# hib_main_7.net
KiCad netlist of a schematic drawn in EAGLE
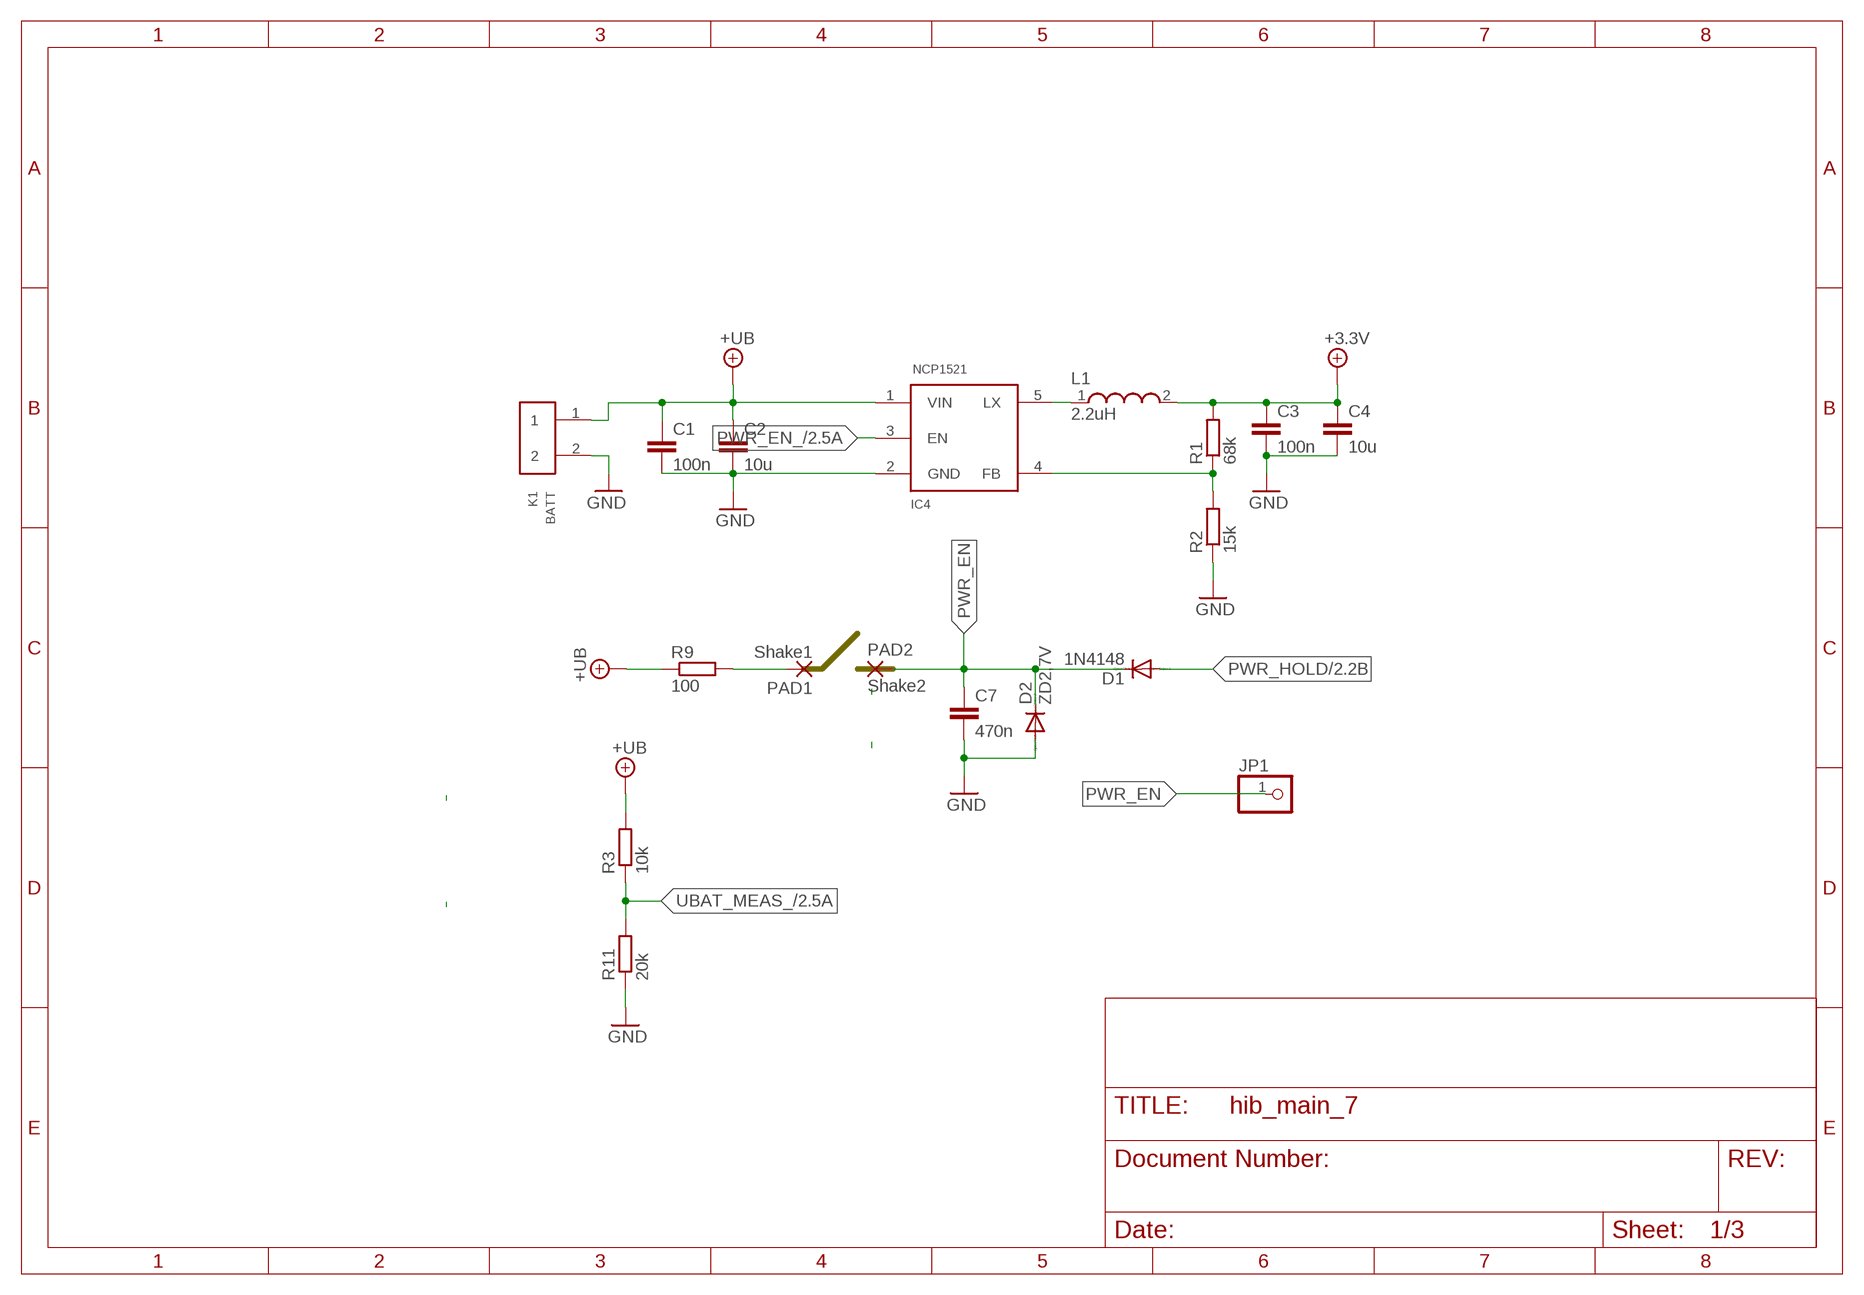
[diagram p0: schematic, sheet 1]
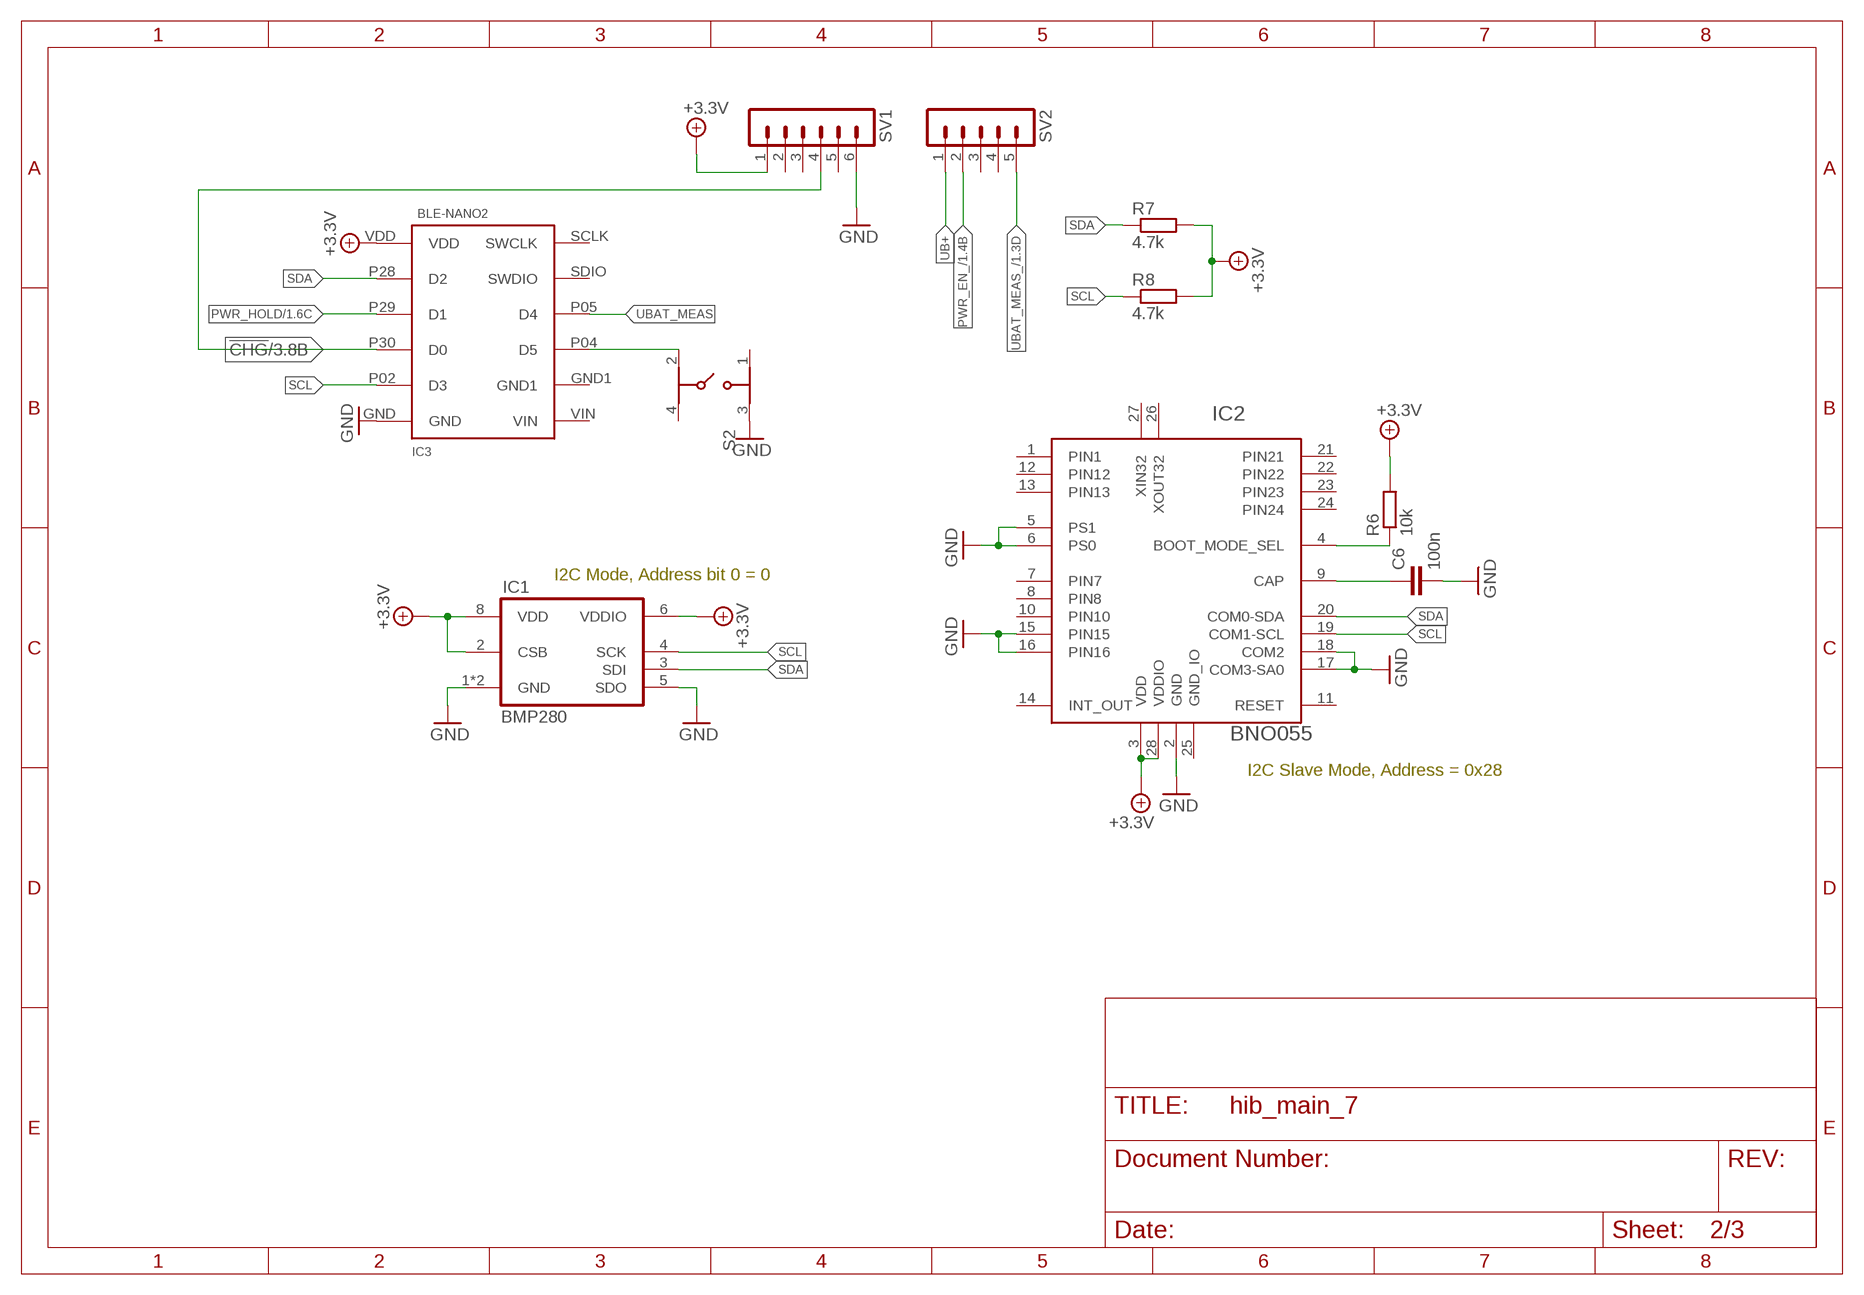
[diagram p1: schematic, sheet 2]
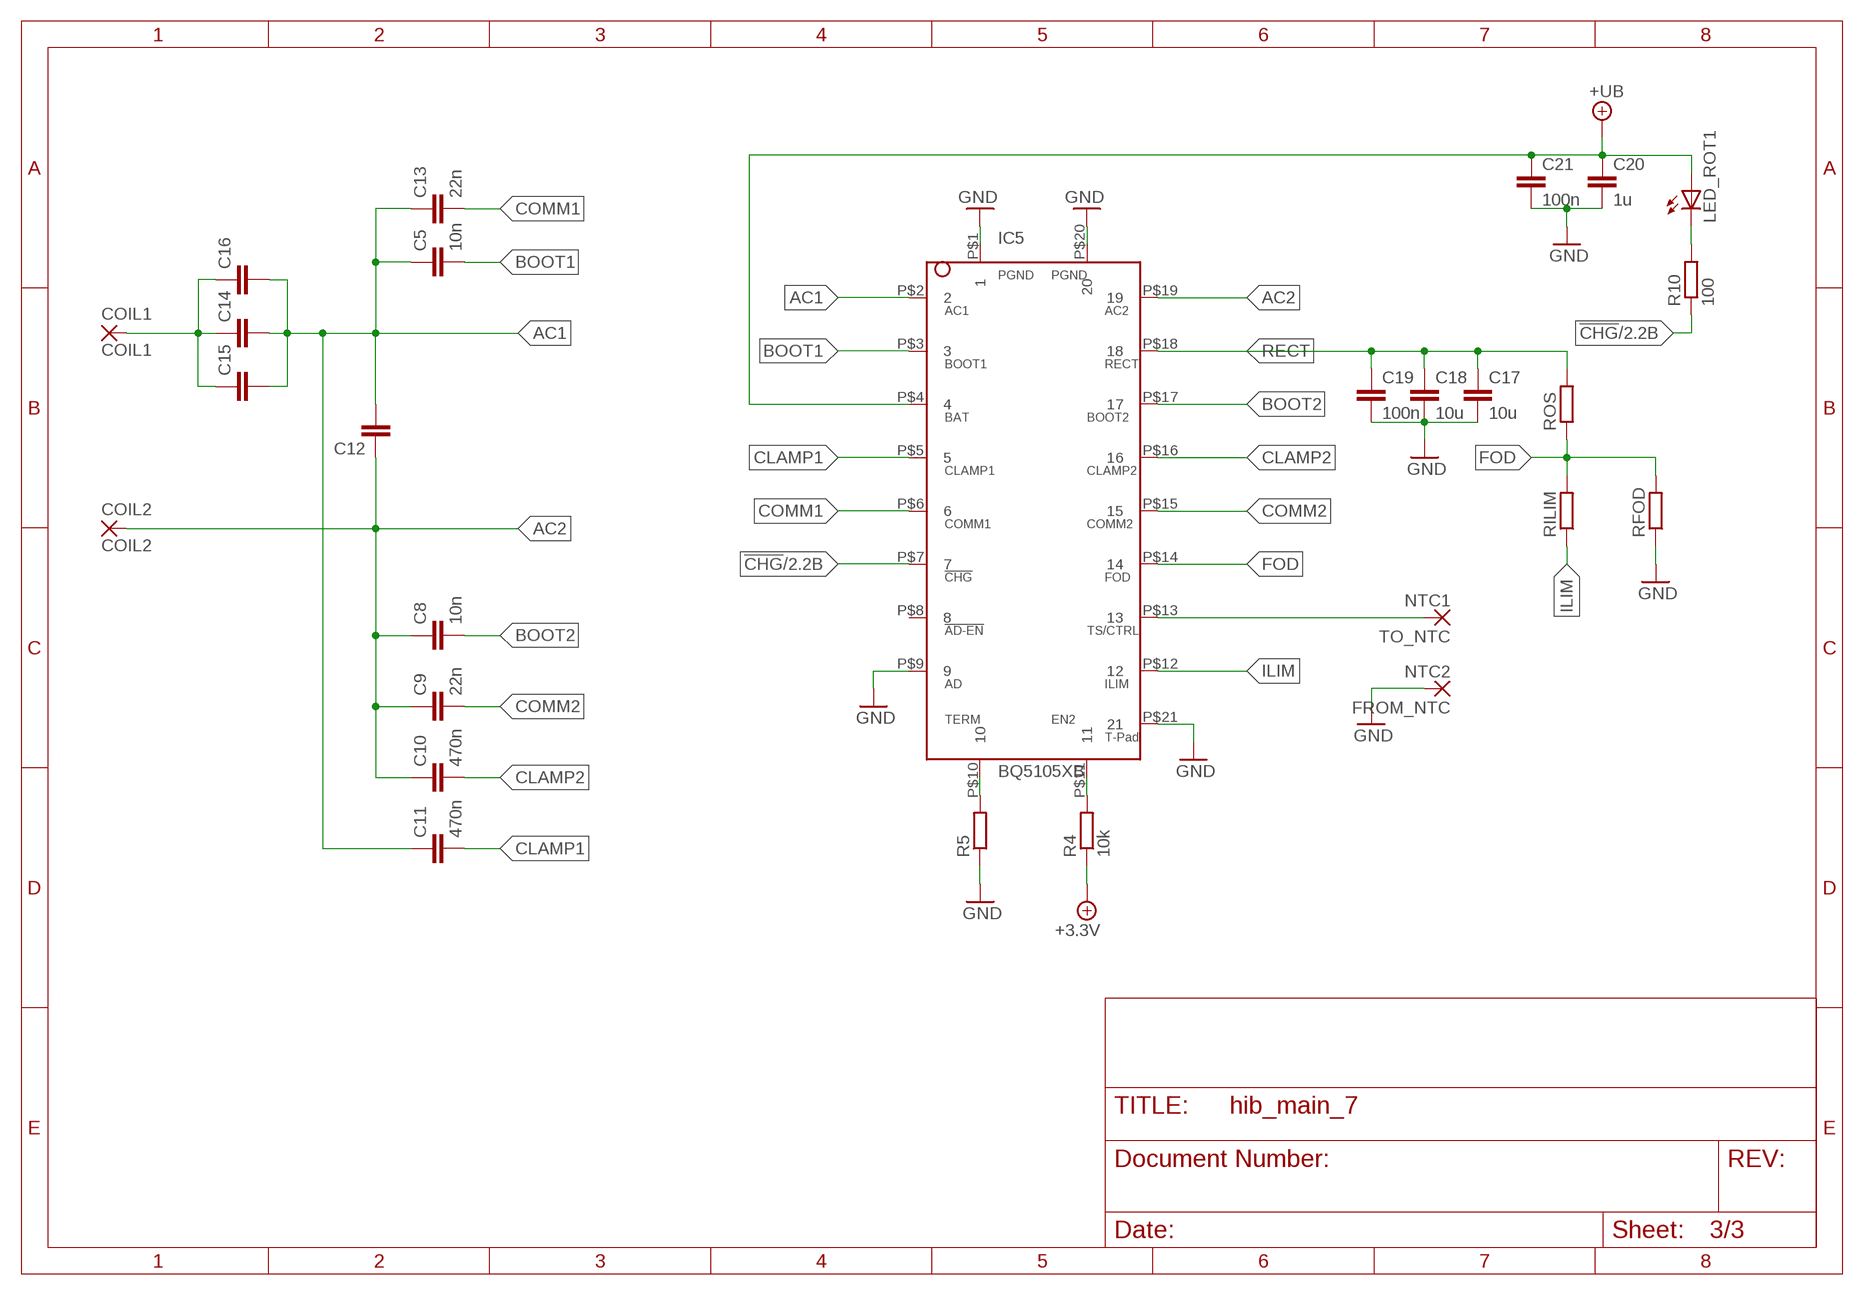
[diagram p2: schematic, sheet 3]

(export (version "E")
  (design (tool "Eeschema 10.0.6"))
  (components
    (comp (ref "C5")
      (value "10n")
      (footprint "eagle-import:C0603K")
      (libsource (lib "eagle-import") (part "rcl@1_C-EUC0603K"))
    )
    (comp (ref "C8")
      (value "10n")
      (footprint "eagle-import:C0603K")
      (libsource (lib "eagle-import") (part "rcl@1_C-EUC0603K"))
    )
    (comp (ref "C9")
      (value "22n")
      (footprint "eagle-import:C0603K")
      (libsource (lib "eagle-import") (part "rcl@1_C-EUC0603K"))
    )
    (comp (ref "C10")
      (value "470n")
      (footprint "eagle-import:C0603K")
      (libsource (lib "eagle-import") (part "rcl@1_C-EUC0603K"))
    )
    (comp (ref "C11")
      (value "470n")
      (footprint "eagle-import:C0603K")
      (libsource (lib "eagle-import") (part "rcl@1_C-EUC0603K"))
    )
    (comp (ref "C12")
      (value "C-EUC0603K")
      (footprint "eagle-import:C0603K")
      (libsource (lib "eagle-import") (part "rcl@1_C-EUC0603K"))
    )
    (comp (ref "C13")
      (value "22n")
      (footprint "eagle-import:C0603K")
      (libsource (lib "eagle-import") (part "rcl@1_C-EUC0603K"))
    )
    (comp (ref "C14")
      (value "C-EUC0603K")
      (footprint "eagle-import:C0603K")
      (libsource (lib "eagle-import") (part "rcl@1_C-EUC0603K"))
    )
    (comp (ref "C15")
      (value "C-EUC0603K")
      (footprint "eagle-import:C0603K")
      (libsource (lib "eagle-import") (part "rcl@1_C-EUC0603K"))
    )
    (comp (ref "C16")
      (value "C-EUC0603K")
      (footprint "eagle-import:C0603K")
      (libsource (lib "eagle-import") (part "rcl@1_C-EUC0603K"))
    )
    (comp (ref "C17")
      (value "10u")
      (footprint "eagle-import:C0603K")
      (libsource (lib "eagle-import") (part "rcl@1_C-EUC0603K"))
    )
    (comp (ref "C18")
      (value "10u")
      (footprint "eagle-import:C0603K")
      (libsource (lib "eagle-import") (part "rcl@1_C-EUC0603K"))
    )
    (comp (ref "C19")
      (value "100n")
      (footprint "eagle-import:C0603K")
      (libsource (lib "eagle-import") (part "rcl@1_C-EUC0603K"))
    )
    (comp (ref "C20")
      (value "1u")
      (footprint "eagle-import:C0603K")
      (libsource (lib "eagle-import") (part "rcl@1_C-EUC0603K"))
    )
    (comp (ref "C21")
      (value "100n")
      (footprint "eagle-import:C0603K")
      (libsource (lib "eagle-import") (part "rcl@1_C-EUC0603K"))
    )
    (comp (ref "COIL1")
      (value "COIL1")
      (footprint "eagle-import:SMD1,27-2,54")
      (libsource (lib "eagle-import") (part "wirepad@1_WIREPADSMD1,27-254"))
    )
    (comp (ref "COIL2")
      (value "COIL2")
      (footprint "eagle-import:SMD1,27-2,54")
      (libsource (lib "eagle-import") (part "wirepad@1_WIREPADSMD1,27-254"))
    )
    (comp (ref "FROM_NTC")
      (value "NTC2")
      (footprint "eagle-import:SMD1,27-2,54")
      (libsource (lib "eagle-import") (part "wirepad@1_WIREPADSMD1,27-254"))
    )
    (comp (ref "IC5")
      (value "BQ5105XB")
      (footprint "eagle-import:VQFN_BQ5105B")
      (libsource (lib "eagle-import") (part "BQ5105XB"))
    )
    (comp (ref "LED_ROT1")
      (value "LEDCHIP-LED0603")
      (footprint "eagle-import:CHIP-LED0603")
      (libsource (lib "eagle-import") (part "LEDCHIP-LED0603"))
    )
    (comp (ref "R4")
      (value "10k")
      (footprint "eagle-import:R0805")
      (libsource (lib "eagle-import") (part "rcl@1_R-EU_R0805"))
    )
    (comp (ref "R5")
      (value "R-EU_R0603")
      (footprint "eagle-import:R0603")
      (libsource (lib "eagle-import") (part "rcl@1_R-EU_R0603"))
    )
    (comp (ref "R10")
      (value "100")
      (footprint "eagle-import:R0603")
      (libsource (lib "eagle-import") (part "rcl@1_R-EU_R0603"))
    )
    (comp (ref "RFOD")
      (value "R-EU_R0805")
      (footprint "eagle-import:R0805")
      (libsource (lib "eagle-import") (part "rcl@1_R-EU_R0805"))
    )
    (comp (ref "RILIM")
      (value "R-EU_R0805")
      (footprint "eagle-import:R0805")
      (libsource (lib "eagle-import") (part "rcl@1_R-EU_R0805"))
    )
    (comp (ref "ROS")
      (value "R-EU_R0805")
      (footprint "eagle-import:R0805")
      (libsource (lib "eagle-import") (part "rcl@1_R-EU_R0805"))
    )
    (comp (ref "TO_NTC")
      (value "NTC1")
      (footprint "eagle-import:SMD1,27-2,54")
      (libsource (lib "eagle-import") (part "wirepad@1_WIREPADSMD1,27-254"))
    )
    (comp (ref "C1")
      (value "100n")
      (footprint "eagle-import:C0805K")
      (libsource (lib "eagle-import") (part "rcl@1_C-EUC0805K"))
    )
    (comp (ref "C2")
      (value "10u")
      (footprint "eagle-import:C0805K")
      (libsource (lib "eagle-import") (part "rcl@1_C-EUC0805K"))
    )
    (comp (ref "C3")
      (value "100n")
      (footprint "eagle-import:C0805M")
      (libsource (lib "eagle-import") (part "C-EUC0805M"))
    )
    (comp (ref "C4")
      (value "10u")
      (footprint "eagle-import:C0805M")
      (libsource (lib "eagle-import") (part "C-EUC0805M"))
    )
    (comp (ref "C7")
      (value "470n")
      (footprint "eagle-import:C0805M")
      (libsource (lib "eagle-import") (part "C-EUC0805M"))
    )
    (comp (ref "D1")
      (value "1N4148")
      (footprint "eagle-import:MINIMELF")
      (libsource (lib "eagle-import") (part "DIODE-MINIMELF"))
    )
    (comp (ref "D2")
      (value "ZD2,7V")
      (footprint "eagle-import:MINIMELF")
      (libsource (lib "eagle-import") (part "DIODE-MINIMELF"))
    )
    (comp (ref "IC4")
      (value "NCP1521")
      (footprint "eagle-import:SOT23-5L")
      (libsource (lib "eagle-import") (part "NCP1521"))
    )
    (comp (ref "JP1")
      (value "PINHD-1X1")
      (footprint "eagle-import:1X01")
      (libsource (lib "eagle-import") (part "PINHD-1X1"))
    )
    (comp (ref "K1")
      (value "BATT")
      (footprint "eagle-import:620102131822")
      (libsource (lib "eagle-import") (part "620102131822"))
    )
    (comp (ref "L1")
      (value "2.2uH")
      (footprint "eagle-import:WE-MPSB_0805(W=4.0)")
      (libsource (lib "eagle-import") (part "WE-MPSB_0805(HC)"))
    )
    (comp (ref "PAD1")
      (value "Shake1")
      (footprint "eagle-import:SMD1,27-2,54")
      (libsource (lib "eagle-import") (part "WIREPADSMD1,27-254"))
    )
    (comp (ref "PAD2")
      (value "Shake2")
      (footprint "eagle-import:SMD1,27-2,54")
      (libsource (lib "eagle-import") (part "WIREPADSMD1,27-254"))
    )
    (comp (ref "R1")
      (value "68k")
      (footprint "eagle-import:R0603")
      (libsource (lib "eagle-import") (part "R-EU_R0603"))
    )
    (comp (ref "R2")
      (value "15k")
      (footprint "eagle-import:R0603")
      (libsource (lib "eagle-import") (part "R-EU_R0603"))
    )
    (comp (ref "R3")
      (value "10k")
      (footprint "eagle-import:R0603")
      (libsource (lib "eagle-import") (part "R-EU_R0603"))
    )
    (comp (ref "R9")
      (value "100")
      (footprint "eagle-import:R0603")
      (libsource (lib "eagle-import") (part "R-EU_R0603"))
    )
    (comp (ref "R11")
      (value "20k")
      (footprint "eagle-import:R0603")
      (libsource (lib "eagle-import") (part "R-EU_R0603"))
    )
    (comp (ref "C6")
      (value "100n")
      (footprint "eagle-import:C0805M")
      (libsource (lib "eagle-import") (part "C-EUC0805M"))
    )
    (comp (ref "IC1")
      (value "BMP280")
      (footprint "eagle-import:BMP280")
      (libsource (lib "eagle-import") (part "BMP280"))
    )
    (comp (ref "IC2")
      (value "BNO055")
      (footprint "eagle-import:LGA-28_3.80X5.20_0.5")
      (libsource (lib "eagle-import") (part "1658_BNO055"))
    )
    (comp (ref "IC3")
      (value "BLE-NANO2")
      (footprint "eagle-import:BLE-NANO2")
      (libsource (lib "eagle-import") (part "BLE-NANO2"))
    )
    (comp (ref "R6")
      (value "10k")
      (footprint "eagle-import:R0805M")
      (libsource (lib "eagle-import") (part "R-EU_R0805M"))
    )
    (comp (ref "R7")
      (value "4.7k")
      (footprint "eagle-import:R0805M")
      (libsource (lib "eagle-import") (part "R-EU_R0805M"))
    )
    (comp (ref "R8")
      (value "4.7k")
      (footprint "eagle-import:R0805M")
      (libsource (lib "eagle-import") (part "R-EU_R0805M"))
    )
    (comp (ref "S2")
      (value "434153017835")
      (footprint "eagle-import:434153017835")
      (libsource (lib "eagle-import") (part "434153017835"))
    )
    (comp (ref "SV1")
      (value "MA06-1")
      (footprint "eagle-import:MA06-1")
      (libsource (lib "eagle-import") (part "MA06-1"))
    )
    (comp (ref "SV2")
      (value "MA05-1")
      (footprint "eagle-import:MA05-1")
      (libsource (lib "eagle-import") (part "MA05-1"))
    )
  )
  (nets
    (net (code "1") (name "+3,3V") (class "Default")
      (node (ref "C3") (pin "1") (pinfunction "1_1") (pintype "passive"))
      (node (ref "C4") (pin "1") (pinfunction "1_1") (pintype "passive"))
      (node (ref "IC1") (pin "2") (pinfunction "CSB_2") (pintype "input"))
      (node (ref "IC1") (pin "6") (pinfunction "VDDIO_6") (pintype "power_in"))
      (node (ref "IC1") (pin "8") (pinfunction "VDD_8") (pintype "power_in"))
      (node (ref "IC2") (pin "28") (pinfunction "VDDIO_28") (pintype "power_in"))
      (node (ref "IC2") (pin "3") (pinfunction "VDD_3") (pintype "power_in"))
      (node (ref "IC3") (pin "VDD") (pinfunction "VDD_VDD") (pintype "bidirectional"))
      (node (ref "L1") (pin "2") (pinfunction "2_2") (pintype "passive"))
      (node (ref "R1") (pin "2") (pinfunction "2_2") (pintype "passive"))
      (node (ref "R4") (pin "1") (pinfunction "1_1") (pintype "passive"))
      (node (ref "R6") (pin "2") (pinfunction "2_2") (pintype "passive"))
      (node (ref "R7") (pin "2") (pinfunction "2_2") (pintype "passive"))
      (node (ref "R8") (pin "2") (pinfunction "2_2") (pintype "passive"))
      (node (ref "SV1") (pin "1") (pinfunction "1_1") (pintype "passive"))
    )
    (net (code "2") (name "+UB") (class "Default")
      (node (ref "C1") (pin "1") (pinfunction "1_1") (pintype "passive"))
      (node (ref "C2") (pin "1") (pinfunction "1_1") (pintype "passive"))
      (node (ref "C20") (pin "1") (pinfunction "1_1") (pintype "passive"))
      (node (ref "C21") (pin "1") (pinfunction "1_1") (pintype "passive"))
      (node (ref "IC4") (pin "1") (pinfunction "VIN_1") (pintype "bidirectional"))
      (node (ref "IC5") (pin "P$4") (pinfunction "4_P$4") (pintype "bidirectional"))
      (node (ref "K1") (pin "1") (pinfunction "1_1") (pintype "passive"))
      (node (ref "LED_ROT1") (pin "A") (pinfunction "A_A") (pintype "passive"))
      (node (ref "R3") (pin "2") (pinfunction "2_2") (pintype "passive"))
      (node (ref "R9") (pin "1") (pinfunction "1_1") (pintype "passive"))
    )
    (net (code "3") (name "AC1") (class "Default")
      (node (ref "C11") (pin "1") (pinfunction "1_1") (pintype "passive"))
      (node (ref "C12") (pin "2") (pinfunction "2_2") (pintype "passive"))
      (node (ref "C13") (pin "1") (pinfunction "1_1") (pintype "passive"))
      (node (ref "C14") (pin "2") (pinfunction "2_2") (pintype "passive"))
      (node (ref "C15") (pin "2") (pinfunction "2_2") (pintype "passive"))
      (node (ref "C16") (pin "2") (pinfunction "2_2") (pintype "passive"))
      (node (ref "C5") (pin "1") (pinfunction "1_1") (pintype "passive"))
      (node (ref "IC5") (pin "P$2") (pinfunction "2_P$2") (pintype "bidirectional"))
    )
    (net (code "4") (name "AC2") (class "Default")
      (node (ref "C10") (pin "1") (pinfunction "1_1") (pintype "passive"))
      (node (ref "C12") (pin "1") (pinfunction "1_1") (pintype "passive"))
      (node (ref "C8") (pin "1") (pinfunction "1_1") (pintype "passive"))
      (node (ref "C9") (pin "1") (pinfunction "1_1") (pintype "passive"))
      (node (ref "COIL2") (pin "1") (pinfunction "P_1") (pintype "passive"))
      (node (ref "IC5") (pin "P$19") (pinfunction "19_P$19") (pintype "bidirectional"))
    )
    (net (code "5") (name "BOOT1") (class "Default")
      (node (ref "C5") (pin "2") (pinfunction "2_2") (pintype "passive"))
      (node (ref "IC5") (pin "P$3") (pinfunction "3_P$3") (pintype "bidirectional"))
    )
    (net (code "6") (name "BOOT2") (class "Default")
      (node (ref "C8") (pin "2") (pinfunction "2_2") (pintype "passive"))
      (node (ref "IC5") (pin "P$17") (pinfunction "17_P$17") (pintype "bidirectional"))
    )
    (net (code "7") (name "CLAMP1") (class "Default")
      (node (ref "C11") (pin "2") (pinfunction "2_2") (pintype "passive"))
      (node (ref "IC5") (pin "P$5") (pinfunction "5_P$5") (pintype "bidirectional"))
    )
    (net (code "8") (name "CLAMP2") (class "Default")
      (node (ref "C10") (pin "2") (pinfunction "2_2") (pintype "passive"))
      (node (ref "IC5") (pin "P$16") (pinfunction "16_P$16") (pintype "bidirectional"))
    )
    (net (code "9") (name "COMM1") (class "Default")
      (node (ref "C13") (pin "2") (pinfunction "2_2") (pintype "passive"))
      (node (ref "IC5") (pin "P$6") (pinfunction "6_P$6") (pintype "bidirectional"))
    )
    (net (code "10") (name "COMM2") (class "Default")
      (node (ref "C9") (pin "2") (pinfunction "2_2") (pintype "passive"))
      (node (ref "IC5") (pin "P$15") (pinfunction "15_P$15") (pintype "bidirectional"))
    )
    (net (code "11") (name "FOD") (class "Default")
      (node (ref "IC5") (pin "P$14") (pinfunction "14_P$14") (pintype "bidirectional"))
      (node (ref "RFOD") (pin "2") (pinfunction "2_2") (pintype "passive"))
      (node (ref "RILIM") (pin "2") (pinfunction "2_2") (pintype "passive"))
      (node (ref "ROS") (pin "1") (pinfunction "1_1") (pintype "passive"))
    )
    (net (code "12") (name "GND") (class "Default")
      (node (ref "C1") (pin "2") (pinfunction "2_2") (pintype "passive"))
      (node (ref "C17") (pin "2") (pinfunction "2_2") (pintype "passive"))
      (node (ref "C18") (pin "2") (pinfunction "2_2") (pintype "passive"))
      (node (ref "C19") (pin "2") (pinfunction "2_2") (pintype "passive"))
      (node (ref "C2") (pin "2") (pinfunction "2_2") (pintype "passive"))
      (node (ref "C20") (pin "2") (pinfunction "2_2") (pintype "passive"))
      (node (ref "C21") (pin "2") (pinfunction "2_2") (pintype "passive"))
      (node (ref "C3") (pin "2") (pinfunction "2_2") (pintype "passive"))
      (node (ref "C4") (pin "2") (pinfunction "2_2") (pintype "passive"))
      (node (ref "C6") (pin "2") (pinfunction "2_2") (pintype "passive"))
      (node (ref "C7") (pin "2") (pinfunction "2_2") (pintype "passive"))
      (node (ref "D2") (pin "A") (pinfunction "A_A") (pintype "passive"))
      (node (ref "FROM_NTC") (pin "1") (pinfunction "P_1") (pintype "passive"))
      (node (ref "IC1") (pin "1") (pinfunction "GND_1") (pintype "power_in"))
      (node (ref "IC1") (pin "5") (pinfunction "SDO_5") (pintype "input"))
      (node (ref "IC1") (pin "7") (pinfunction "GND_7") (pintype "power_in"))
      (node (ref "IC2") (pin "15") (pinfunction "PIN15_15") (pintype "passive"))
      (node (ref "IC2") (pin "16") (pinfunction "PIN16_16") (pintype "passive"))
      (node (ref "IC2") (pin "17") (pinfunction "COM3-SA0_17") (pintype "bidirectional"))
      (node (ref "IC2") (pin "18") (pinfunction "COM2_18") (pintype "bidirectional"))
      (node (ref "IC2") (pin "2") (pinfunction "GND_2") (pintype "power_in"))
      (node (ref "IC2") (pin "5") (pinfunction "PS1_5") (pintype "input"))
      (node (ref "IC2") (pin "6") (pinfunction "PS0_6") (pintype "input"))
      (node (ref "IC3") (pin "GND") (pinfunction "GND_GND") (pintype "bidirectional"))
      (node (ref "IC4") (pin "2") (pinfunction "GND_2") (pintype "bidirectional"))
      (node (ref "IC5") (pin "P$1") (pinfunction "1_P$1") (pintype "bidirectional"))
      (node (ref "IC5") (pin "P$20") (pinfunction "20_P$20") (pintype "bidirectional"))
      (node (ref "IC5") (pin "P$21") (pinfunction "21_P$21") (pintype "bidirectional"))
      (node (ref "IC5") (pin "P$9") (pinfunction "9_P$9") (pintype "bidirectional"))
      (node (ref "K1") (pin "2") (pinfunction "2_2") (pintype "passive"))
      (node (ref "R11") (pin "1") (pinfunction "1_1") (pintype "passive"))
      (node (ref "R2") (pin "1") (pinfunction "1_1") (pintype "passive"))
      (node (ref "R5") (pin "1") (pinfunction "1_1") (pintype "passive"))
      (node (ref "RFOD") (pin "1") (pinfunction "1_1") (pintype "passive"))
      (node (ref "S2") (pin "3") (pinfunction "2_3") (pintype "passive"))
      (node (ref "SV1") (pin "6") (pinfunction "6_6") (pintype "passive"))
    )
    (net (code "13") (name "GND_IO") (class "Default")
      (node (ref "IC2") (pin "25") (pinfunction "GND_IO_25") (pintype "power_in"))
    )
    (net (code "14") (name "ILIM") (class "Default")
      (node (ref "IC5") (pin "P$12") (pinfunction "12_P$12") (pintype "bidirectional"))
      (node (ref "RILIM") (pin "1") (pinfunction "1_1") (pintype "passive"))
    )
    (net (code "15") (name "Net-(COIL1-P)") (class "Default")
      (node (ref "C14") (pin "1") (pinfunction "1_1") (pintype "passive"))
      (node (ref "C15") (pin "1") (pinfunction "1_1") (pintype "passive"))
      (node (ref "C16") (pin "1") (pinfunction "1_1") (pintype "passive"))
      (node (ref "COIL1") (pin "1") (pinfunction "P_1") (pintype "passive"))
    )
    (net (code "16") (name "Net-(IC2-BOOT_MODE_SEL)") (class "Default")
      (node (ref "IC2") (pin "4") (pinfunction "BOOT_MODE_SEL_4") (pintype "input"))
      (node (ref "R6") (pin "1") (pinfunction "1_1") (pintype "passive"))
    )
    (net (code "17") (name "Net-(IC2-CAP)") (class "Default")
      (node (ref "C6") (pin "1") (pinfunction "1_1") (pintype "passive"))
      (node (ref "IC2") (pin "9") (pinfunction "CAP_9") (pintype "tri_state"))
    )
    (net (code "18") (name "Net-(IC3-D5)") (class "Default")
      (node (ref "IC3") (pin "P04") (pinfunction "D5_P04") (pintype "bidirectional"))
      (node (ref "S2") (pin "2") (pinfunction "3_2") (pintype "passive"))
    )
    (net (code "19") (name "Net-(IC4-FB)") (class "Default")
      (node (ref "IC4") (pin "4") (pinfunction "FB_4") (pintype "bidirectional"))
      (node (ref "R1") (pin "1") (pinfunction "1_1") (pintype "passive"))
      (node (ref "R2") (pin "2") (pinfunction "2_2") (pintype "passive"))
    )
    (net (code "20") (name "Net-(IC4-LX)") (class "Default")
      (node (ref "IC4") (pin "5") (pinfunction "LX_5") (pintype "bidirectional"))
      (node (ref "L1") (pin "1") (pinfunction "1_1") (pintype "passive"))
    )
    (net (code "21") (name "Net-(IC5-10)") (class "Default")
      (node (ref "IC5") (pin "P$10") (pinfunction "10_P$10") (pintype "bidirectional"))
      (node (ref "R5") (pin "2") (pinfunction "2_2") (pintype "passive"))
    )
    (net (code "22") (name "Net-(IC5-11)") (class "Default")
      (node (ref "IC5") (pin "P$11") (pinfunction "11_P$11") (pintype "bidirectional"))
      (node (ref "R4") (pin "2") (pinfunction "2_2") (pintype "passive"))
    )
    (net (code "23") (name "Net-(IC5-13)") (class "Default")
      (node (ref "IC5") (pin "P$13") (pinfunction "13_P$13") (pintype "bidirectional"))
      (node (ref "TO_NTC") (pin "1") (pinfunction "P_1") (pintype "passive"))
    )
    (net (code "24") (name "Net-(LED_ROT1-PadC)") (class "Default")
      (node (ref "LED_ROT1") (pin "C") (pinfunction "C_C") (pintype "passive"))
      (node (ref "R10") (pin "2") (pinfunction "2_2") (pintype "passive"))
    )
    (net (code "25") (name "Net-(PAD1-P)") (class "Default")
      (node (ref "PAD1") (pin "1") (pinfunction "P_1") (pintype "passive"))
      (node (ref "R9") (pin "2") (pinfunction "2_2") (pintype "passive"))
    )
    (net (code "26") (name "PWR_EN") (class "Default")
      (node (ref "C7") (pin "1") (pinfunction "1_1") (pintype "passive"))
      (node (ref "D1") (pin "C") (pinfunction "C_C") (pintype "passive"))
      (node (ref "D2") (pin "C") (pinfunction "C_C") (pintype "passive"))
      (node (ref "JP1") (pin "1") (pinfunction "1_1") (pintype "passive"))
      (node (ref "PAD2") (pin "1") (pinfunction "P_1") (pintype "passive"))
    )
    (net (code "27") (name "PWR_EN_") (class "Default")
      (node (ref "IC4") (pin "3") (pinfunction "EN_3") (pintype "bidirectional"))
      (node (ref "SV2") (pin "2") (pinfunction "2_2") (pintype "passive"))
    )
    (net (code "28") (name "PWR_HOLD") (class "Default")
      (node (ref "D1") (pin "A") (pinfunction "A_A") (pintype "passive"))
      (node (ref "IC3") (pin "P29") (pinfunction "D1_P29") (pintype "bidirectional"))
    )
    (net (code "29") (name "RECT") (class "Default")
      (node (ref "C17") (pin "1") (pinfunction "1_1") (pintype "passive"))
      (node (ref "C18") (pin "1") (pinfunction "1_1") (pintype "passive"))
      (node (ref "C19") (pin "1") (pinfunction "1_1") (pintype "passive"))
      (node (ref "IC5") (pin "P$18") (pinfunction "18_P$18") (pintype "bidirectional"))
      (node (ref "ROS") (pin "2") (pinfunction "2_2") (pintype "passive"))
    )
    (net (code "30") (name "SCL") (class "Default")
      (node (ref "IC1") (pin "4") (pinfunction "SCK_4") (pintype "bidirectional"))
      (node (ref "IC2") (pin "19") (pinfunction "COM1-SCL_19") (pintype "bidirectional"))
      (node (ref "IC3") (pin "P02") (pinfunction "D3_P02") (pintype "bidirectional"))
      (node (ref "R8") (pin "1") (pinfunction "1_1") (pintype "passive"))
    )
    (net (code "31") (name "SDA") (class "Default")
      (node (ref "IC1") (pin "3") (pinfunction "SDI_3") (pintype "bidirectional"))
      (node (ref "IC2") (pin "20") (pinfunction "COM0-SDA_20") (pintype "bidirectional"))
      (node (ref "IC3") (pin "P28") (pinfunction "D2_P28") (pintype "bidirectional"))
      (node (ref "R7") (pin "1") (pinfunction "1_1") (pintype "passive"))
    )
    (net (code "32") (name "UB+") (class "Default")
      (node (ref "SV2") (pin "1") (pinfunction "1_1") (pintype "passive"))
    )
    (net (code "33") (name "UBAT_MEAS") (class "Default")
      (node (ref "IC3") (pin "P05") (pinfunction "D4_P05") (pintype "bidirectional"))
    )
    (net (code "34") (name "UBAT_MEAS_") (class "Default")
      (node (ref "R11") (pin "2") (pinfunction "2_2") (pintype "passive"))
      (node (ref "R3") (pin "1") (pinfunction "1_1") (pintype "passive"))
      (node (ref "SV2") (pin "5") (pinfunction "5_5") (pintype "passive"))
    )
    (net (code "35") (name "unconnected-(IC2-INT_OUT-Pad14)") (class "Default")
      (node (ref "IC2") (pin "14") (pinfunction "INT_OUT_14") (pintype "output"))
    )
    (net (code "36") (name "unconnected-(IC2-PIN1-Pad1)") (class "Default")
      (node (ref "IC2") (pin "1") (pinfunction "PIN1_1") (pintype "no_connect"))
    )
    (net (code "37") (name "unconnected-(IC2-PIN7-Pad7)") (class "Default")
      (node (ref "IC2") (pin "7") (pinfunction "PIN7_7") (pintype "tri_state"))
    )
    (net (code "38") (name "unconnected-(IC2-PIN8-Pad8)") (class "Default")
      (node (ref "IC2") (pin "8") (pinfunction "PIN8_8") (pintype "tri_state"))
    )
    (net (code "39") (name "unconnected-(IC2-PIN10-Pad10)") (class "Default")
      (node (ref "IC2") (pin "10") (pinfunction "PIN10_10") (pintype "passive"))
    )
    (net (code "40") (name "unconnected-(IC2-PIN12-Pad12)") (class "Default")
      (node (ref "IC2") (pin "12") (pinfunction "PIN12_12") (pintype "passive"))
    )
    (net (code "41") (name "unconnected-(IC2-PIN13-Pad13)") (class "Default")
      (node (ref "IC2") (pin "13") (pinfunction "PIN13_13") (pintype "passive"))
    )
    (net (code "42") (name "unconnected-(IC2-PIN21-Pad21)") (class "Default")
      (node (ref "IC2") (pin "21") (pinfunction "PIN21_21") (pintype "passive"))
    )
    (net (code "43") (name "unconnected-(IC2-PIN22-Pad22)") (class "Default")
      (node (ref "IC2") (pin "22") (pinfunction "PIN22_22") (pintype "passive"))
    )
    (net (code "44") (name "unconnected-(IC2-PIN23-Pad23)") (class "Default")
      (node (ref "IC2") (pin "23") (pinfunction "PIN23_23") (pintype "passive"))
    )
    (net (code "45") (name "unconnected-(IC2-PIN24-Pad24)") (class "Default")
      (node (ref "IC2") (pin "24") (pinfunction "PIN24_24") (pintype "passive"))
    )
    (net (code "46") (name "unconnected-(IC2-RESET-Pad11)") (class "Default")
      (node (ref "IC2") (pin "11") (pinfunction "RESET_11") (pintype "input"))
    )
    (net (code "47") (name "unconnected-(IC2-XIN32-Pad27)") (class "Default")
      (node (ref "IC2") (pin "27") (pinfunction "XIN32_27") (pintype "bidirectional"))
    )
    (net (code "48") (name "unconnected-(IC2-XOUT32-Pad26)") (class "Default")
      (node (ref "IC2") (pin "26") (pinfunction "XOUT32_26") (pintype "output"))
    )
    (net (code "49") (name "unconnected-(IC3-PadGND1)") (class "Default")
      (node (ref "IC3") (pin "GND1") (pinfunction "GND1_GND1") (pintype "bidirectional"))
    )
    (net (code "50") (name "unconnected-(IC3-PadVIN)") (class "Default")
      (node (ref "IC3") (pin "VIN") (pinfunction "VIN_VIN") (pintype "bidirectional"))
    )
    (net (code "51") (name "unconnected-(IC3-SWCLK-PadSCLK)") (class "Default")
      (node (ref "IC3") (pin "SCLK") (pinfunction "SWCLK_SCLK") (pintype "bidirectional"))
    )
    (net (code "52") (name "unconnected-(IC3-SWDIO-PadSDIO)") (class "Default")
      (node (ref "IC3") (pin "SDIO") (pinfunction "SWDIO_SDIO") (pintype "bidirectional"))
    )
    (net (code "53") (name "unconnected-(IC5-8-PadP$8)") (class "Default")
      (node (ref "IC5") (pin "P$8") (pinfunction "8_P$8") (pintype "bidirectional"))
    )
    (net (code "54") (name "unconnected-(S2-Pad1)") (class "Default")
      (node (ref "S2") (pin "1") (pinfunction "1_1") (pintype "passive"))
    )
    (net (code "55") (name "unconnected-(S2-Pad4)") (class "Default")
      (node (ref "S2") (pin "4") (pinfunction "4_4") (pintype "passive"))
    )
    (net (code "56") (name "unconnected-(SV1-Pad2)") (class "Default")
      (node (ref "SV1") (pin "2") (pinfunction "2_2") (pintype "passive"))
    )
    (net (code "57") (name "unconnected-(SV1-Pad3)") (class "Default")
      (node (ref "SV1") (pin "3") (pinfunction "3_3") (pintype "passive"))
    )
    (net (code "58") (name "unconnected-(SV1-Pad5)") (class "Default")
      (node (ref "SV1") (pin "5") (pinfunction "5_5") (pintype "passive"))
    )
    (net (code "59") (name "unconnected-(SV2-Pad3)") (class "Default")
      (node (ref "SV2") (pin "3") (pinfunction "3_3") (pintype "passive"))
    )
    (net (code "60") (name "unconnected-(SV2-Pad4)") (class "Default")
      (node (ref "SV2") (pin "4") (pinfunction "4_4") (pintype "passive"))
    )
    (net (code "61") (name "~{CHG}") (class "Default")
      (node (ref "IC3") (pin "P30") (pinfunction "D0_P30") (pintype "bidirectional"))
      (node (ref "IC5") (pin "P$7") (pinfunction "7_P$7") (pintype "bidirectional"))
      (node (ref "R10") (pin "1") (pinfunction "1_1") (pintype "passive"))
      (node (ref "SV1") (pin "4") (pinfunction "4_4") (pintype "passive"))
    )
  )
)
